# Rs232Iso.net
KiCad netlist of a schematic drawn in EAGLE
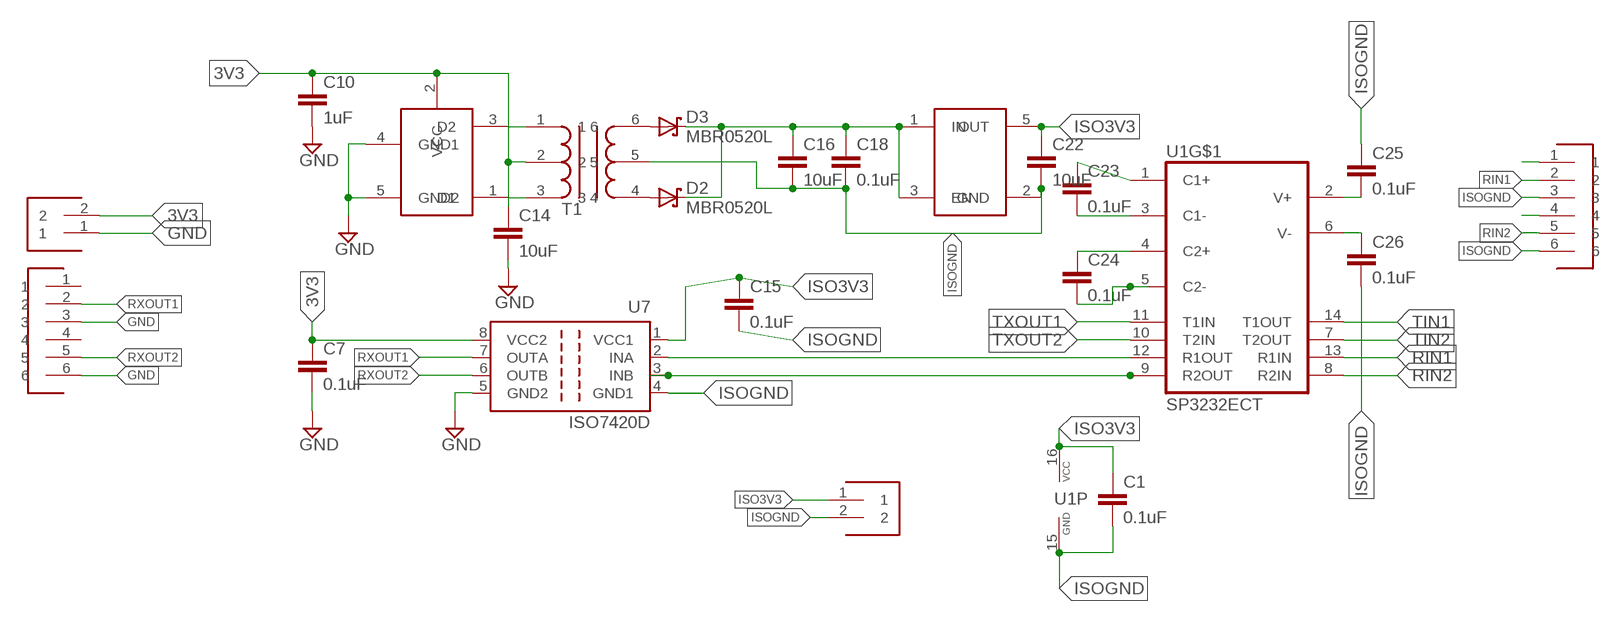
[diagram p0: schematic, sheet 1]

(export (version "E")
  (design (tool "Eeschema 10.0.6"))
  (components
    (comp (ref "C1")
      (value "0.1uF")
      (footprint "eagle-import:0805")
      (libsource (lib "eagle-import") (part "CAP0805"))
    )
    (comp (ref "C7")
      (value "0.1uF")
      (footprint "eagle-import:0805")
      (libsource (lib "eagle-import") (part "CAP0805"))
    )
    (comp (ref "C10")
      (value "1uF")
      (footprint "eagle-import:0805")
      (libsource (lib "eagle-import") (part "CAP0805"))
    )
    (comp (ref "C14")
      (value "10uF")
      (footprint "eagle-import:0805")
      (libsource (lib "eagle-import") (part "CAP0805"))
    )
    (comp (ref "C15")
      (value "0.1uF")
      (footprint "eagle-import:0805")
      (libsource (lib "eagle-import") (part "CAP0805"))
    )
    (comp (ref "C16")
      (value "10uF")
      (footprint "eagle-import:0805")
      (libsource (lib "eagle-import") (part "CAP0805"))
    )
    (comp (ref "C18")
      (value "0.1uF")
      (footprint "eagle-import:0805")
      (libsource (lib "eagle-import") (part "CAP0805"))
    )
    (comp (ref "C22")
      (value "10uF")
      (footprint "eagle-import:0805")
      (libsource (lib "eagle-import") (part "CAP0805"))
    )
    (comp (ref "C23")
      (value "0.1uF")
      (footprint "eagle-import:0805")
      (libsource (lib "eagle-import") (part "CAP0805"))
    )
    (comp (ref "C24")
      (value "0.1uF")
      (footprint "eagle-import:0805")
      (libsource (lib "eagle-import") (part "CAP0805"))
    )
    (comp (ref "C25")
      (value "0.1uF")
      (footprint "eagle-import:0805")
      (libsource (lib "eagle-import") (part "CAP0805"))
    )
    (comp (ref "C26")
      (value "0.1uF")
      (footprint "eagle-import:0805")
      (libsource (lib "eagle-import") (part "CAP0805"))
    )
    (comp (ref "D2")
      (value "MBR0520L")
      (footprint "eagle-import:SOD123")
      (libsource (lib "eagle-import") (part "MBR0520L"))
    )
    (comp (ref "D3")
      (value "MBR0520L")
      (footprint "eagle-import:SOD123")
      (libsource (lib "eagle-import") (part "MBR0520L"))
    )
    (comp (ref "J1")
      (value "CON-2")
      (footprint "eagle-import:CON-2")
      (libsource (lib "eagle-import") (part "CON-2"))
    )
    (comp (ref "J2")
      (value "CON-6")
      (footprint "eagle-import:CON-6")
      (libsource (lib "eagle-import") (part "CON-6"))
    )
    (comp (ref "J3")
      (value "CON-2")
      (footprint "eagle-import:CON-2")
      (libsource (lib "eagle-import") (part "CON-2"))
    )
    (comp (ref "J4")
      (value "CON-6")
      (footprint "eagle-import:CON-6")
      (libsource (lib "eagle-import") (part "CON-6"))
    )
    (comp (ref "T1")
      (value "WE-PP-ISO-TRANSFORMER760390011")
      (footprint "eagle-import:WE_TRANSFORMER")
      (libsource (lib "eagle-import") (part "WE-PP-ISO-TRANSFORMER760390011"))
    )
    (comp (ref "U1")
      (value "SP3232ECT")
      (footprint "eagle-import:SO16")
      (libsource (lib "eagle-import") (part "SP3232ECT"))
    )
    (comp (ref "U2")
      (value "TPS76333")
      (footprint "eagle-import:SOT23-5L")
      (libsource (lib "eagle-import") (part "TPS76333"))
    )
    (comp (ref "U5")
      (value "SN6501DBVT")
      (footprint "eagle-import:SOT23-5L")
      (libsource (lib "eagle-import") (part "SN6501DBVT"))
    )
    (comp (ref "U7")
      (value "ISO7420D")
      (footprint "eagle-import:SO08")
      (libsource (lib "eagle-import") (part "ISO7420D"))
    )
  )
  (nets
    (net (code "1") (name "3V3") (class "Default")
      (node (ref "C10") (pin "1") (pinfunction "1_1") (pintype "passive"))
      (node (ref "C14") (pin "1") (pinfunction "1_1") (pintype "passive"))
      (node (ref "C7") (pin "1") (pinfunction "1_1") (pintype "passive"))
      (node (ref "J1") (pin "2") (pinfunction "2_2") (pintype "bidirectional"))
      (node (ref "T1") (pin "2") (pinfunction "2_2") (pintype "input"))
      (node (ref "U5") (pin "2") (pinfunction "VCC_2") (pintype "bidirectional"))
      (node (ref "U7") (pin "8") (pinfunction "VCC2_8") (pintype "power_in"))
    )
    (net (code "2") (name "GND") (class "Default")
      (node (ref "C10") (pin "2") (pinfunction "2_2") (pintype "passive"))
      (node (ref "C14") (pin "2") (pinfunction "2_2") (pintype "passive"))
      (node (ref "C7") (pin "2") (pinfunction "2_2") (pintype "passive"))
      (node (ref "J1") (pin "1") (pinfunction "1_1") (pintype "bidirectional"))
      (node (ref "J4") (pin "3") (pinfunction "3_3") (pintype "bidirectional"))
      (node (ref "J4") (pin "6") (pinfunction "6_6") (pintype "bidirectional"))
      (node (ref "U5") (pin "4") (pinfunction "GND1_4") (pintype "bidirectional"))
      (node (ref "U5") (pin "5") (pinfunction "GND2_5") (pintype "bidirectional"))
      (node (ref "U7") (pin "5") (pinfunction "GND2_5") (pintype "power_in"))
    )
    (net (code "3") (name "ISO3V3") (class "Default")
      (node (ref "C1") (pin "1") (pinfunction "1_1") (pintype "passive"))
      (node (ref "C15") (pin "1") (pinfunction "1_1") (pintype "passive"))
      (node (ref "C22") (pin "1") (pinfunction "1_1") (pintype "passive"))
      (node (ref "J3") (pin "1") (pinfunction "1_1") (pintype "bidirectional"))
      (node (ref "U1") (pin "16") (pinfunction "VCC_16") (pintype "power_in"))
      (node (ref "U2") (pin "5") (pinfunction "OUT_5") (pintype "bidirectional"))
      (node (ref "U7") (pin "1") (pinfunction "VCC1_1") (pintype "power_in"))
    )
    (net (code "4") (name "ISOGND") (class "Default")
      (node (ref "C1") (pin "2") (pinfunction "2_2") (pintype "passive"))
      (node (ref "C15") (pin "2") (pinfunction "2_2") (pintype "passive"))
      (node (ref "C16") (pin "2") (pinfunction "2_2") (pintype "passive"))
      (node (ref "C18") (pin "2") (pinfunction "2_2") (pintype "passive"))
      (node (ref "C22") (pin "2") (pinfunction "2_2") (pintype "passive"))
      (node (ref "C25") (pin "1") (pinfunction "1_1") (pintype "passive"))
      (node (ref "C26") (pin "2") (pinfunction "2_2") (pintype "passive"))
      (node (ref "J2") (pin "3") (pinfunction "3_3") (pintype "bidirectional"))
      (node (ref "J2") (pin "6") (pinfunction "6_6") (pintype "bidirectional"))
      (node (ref "J3") (pin "2") (pinfunction "2_2") (pintype "bidirectional"))
      (node (ref "T1") (pin "5") (pinfunction "5_5") (pintype "passive"))
      (node (ref "U1") (pin "15") (pinfunction "GND_15") (pintype "power_in"))
      (node (ref "U2") (pin "2") (pinfunction "GND_2") (pintype "bidirectional"))
      (node (ref "U7") (pin "4") (pinfunction "GND1_4") (pintype "power_in"))
    )
    (net (code "5") (name "Net-(D2-PadA)") (class "Default")
      (node (ref "D2") (pin "A") (pinfunction "A_A") (pintype "passive"))
      (node (ref "T1") (pin "4") (pinfunction "4_4") (pintype "passive"))
    )
    (net (code "6") (name "Net-(D3-PadA)") (class "Default")
      (node (ref "D3") (pin "A") (pinfunction "A_A") (pintype "passive"))
      (node (ref "T1") (pin "6") (pinfunction "6_6") (pintype "passive"))
    )
    (net (code "7") (name "Net-(U1A-C1+)") (class "Default")
      (node (ref "C23") (pin "1") (pinfunction "1_1") (pintype "passive"))
      (node (ref "U1") (pin "1") (pinfunction "C1+_1") (pintype "bidirectional"))
    )
    (net (code "8") (name "Net-(U1A-C1-)") (class "Default")
      (node (ref "C23") (pin "2") (pinfunction "2_2") (pintype "passive"))
      (node (ref "U1") (pin "3") (pinfunction "C1-_3") (pintype "bidirectional"))
    )
    (net (code "9") (name "Net-(U1A-C2+)") (class "Default")
      (node (ref "C24") (pin "1") (pinfunction "1_1") (pintype "passive"))
      (node (ref "U1") (pin "4") (pinfunction "C2+_4") (pintype "bidirectional"))
    )
    (net (code "10") (name "Net-(U1A-C2-)") (class "Default")
      (node (ref "C24") (pin "2") (pinfunction "2_2") (pintype "passive"))
      (node (ref "U1") (pin "5") (pinfunction "C2-_5") (pintype "bidirectional"))
    )
    (net (code "11") (name "Net-(U1A-R1OUT)") (class "Default")
      (node (ref "U1") (pin "12") (pinfunction "R1OUT_12") (pintype "output"))
      (node (ref "U7") (pin "2") (pinfunction "INA_2") (pintype "input"))
    )
    (net (code "12") (name "Net-(U1A-R2OUT)") (class "Default")
      (node (ref "U1") (pin "9") (pinfunction "R2OUT_9") (pintype "output"))
      (node (ref "U7") (pin "3") (pinfunction "INB_3") (pintype "input"))
    )
    (net (code "13") (name "Net-(U1A-V+)") (class "Default")
      (node (ref "C25") (pin "2") (pinfunction "2_2") (pintype "passive"))
      (node (ref "U1") (pin "2") (pinfunction "V+_2") (pintype "bidirectional"))
    )
    (net (code "14") (name "Net-(U1A-V-)") (class "Default")
      (node (ref "C26") (pin "1") (pinfunction "1_1") (pintype "passive"))
      (node (ref "U1") (pin "6") (pinfunction "V-_6") (pintype "bidirectional"))
    )
    (net (code "15") (name "Net-(U2-EN)") (class "Default")
      (node (ref "C16") (pin "1") (pinfunction "1_1") (pintype "passive"))
      (node (ref "C18") (pin "1") (pinfunction "1_1") (pintype "passive"))
      (node (ref "D2") (pin "C") (pinfunction "C_C") (pintype "passive"))
      (node (ref "D3") (pin "C") (pinfunction "C_C") (pintype "passive"))
      (node (ref "U2") (pin "1") (pinfunction "IN_1") (pintype "bidirectional"))
      (node (ref "U2") (pin "3") (pinfunction "EN_3") (pintype "bidirectional"))
    )
    (net (code "16") (name "Net-(U5-D1)") (class "Default")
      (node (ref "T1") (pin "3") (pinfunction "3_3") (pintype "input"))
      (node (ref "U5") (pin "1") (pinfunction "D1_1") (pintype "bidirectional"))
    )
    (net (code "17") (name "Net-(U5-D2)") (class "Default")
      (node (ref "T1") (pin "1") (pinfunction "1_1") (pintype "input"))
      (node (ref "U5") (pin "3") (pinfunction "D2_3") (pintype "bidirectional"))
    )
    (net (code "18") (name "RIN1") (class "Default")
      (node (ref "J2") (pin "2") (pinfunction "2_2") (pintype "bidirectional"))
      (node (ref "U1") (pin "13") (pinfunction "R1IN_13") (pintype "input"))
    )
    (net (code "19") (name "RIN2") (class "Default")
      (node (ref "J2") (pin "5") (pinfunction "5_5") (pintype "bidirectional"))
      (node (ref "U1") (pin "8") (pinfunction "R2IN_8") (pintype "input"))
    )
    (net (code "20") (name "RXOUT1") (class "Default")
      (node (ref "J4") (pin "2") (pinfunction "2_2") (pintype "bidirectional"))
      (node (ref "U7") (pin "7") (pinfunction "OUTA_7") (pintype "output"))
    )
    (net (code "21") (name "RXOUT2") (class "Default")
      (node (ref "J4") (pin "5") (pinfunction "5_5") (pintype "bidirectional"))
      (node (ref "U7") (pin "6") (pinfunction "OUTB_6") (pintype "output"))
    )
    (net (code "22") (name "TIN1") (class "Default")
      (node (ref "U1") (pin "14") (pinfunction "T1OUT_14") (pintype "output"))
    )
    (net (code "23") (name "TIN2") (class "Default")
      (node (ref "U1") (pin "7") (pinfunction "T2OUT_7") (pintype "output"))
    )
    (net (code "24") (name "TXOUT1") (class "Default")
      (node (ref "U1") (pin "11") (pinfunction "T1IN_11") (pintype "input"))
    )
    (net (code "25") (name "TXOUT2") (class "Default")
      (node (ref "U1") (pin "10") (pinfunction "T2IN_10") (pintype "input"))
    )
    (net (code "26") (name "unconnected-(J2-Pad1)") (class "Default")
      (node (ref "J2") (pin "1") (pinfunction "1_1") (pintype "bidirectional"))
    )
    (net (code "27") (name "unconnected-(J2-Pad4)") (class "Default")
      (node (ref "J2") (pin "4") (pinfunction "4_4") (pintype "bidirectional"))
    )
    (net (code "28") (name "unconnected-(J4-Pad1)") (class "Default")
      (node (ref "J4") (pin "1") (pinfunction "1_1") (pintype "bidirectional"))
    )
    (net (code "29") (name "unconnected-(J4-Pad4)") (class "Default")
      (node (ref "J4") (pin "4") (pinfunction "4_4") (pintype "bidirectional"))
    )
  )
)
